# YOTSUBA_AP_EM_ver_3_0.net
KiCad netlist of a schematic drawn in EAGLE
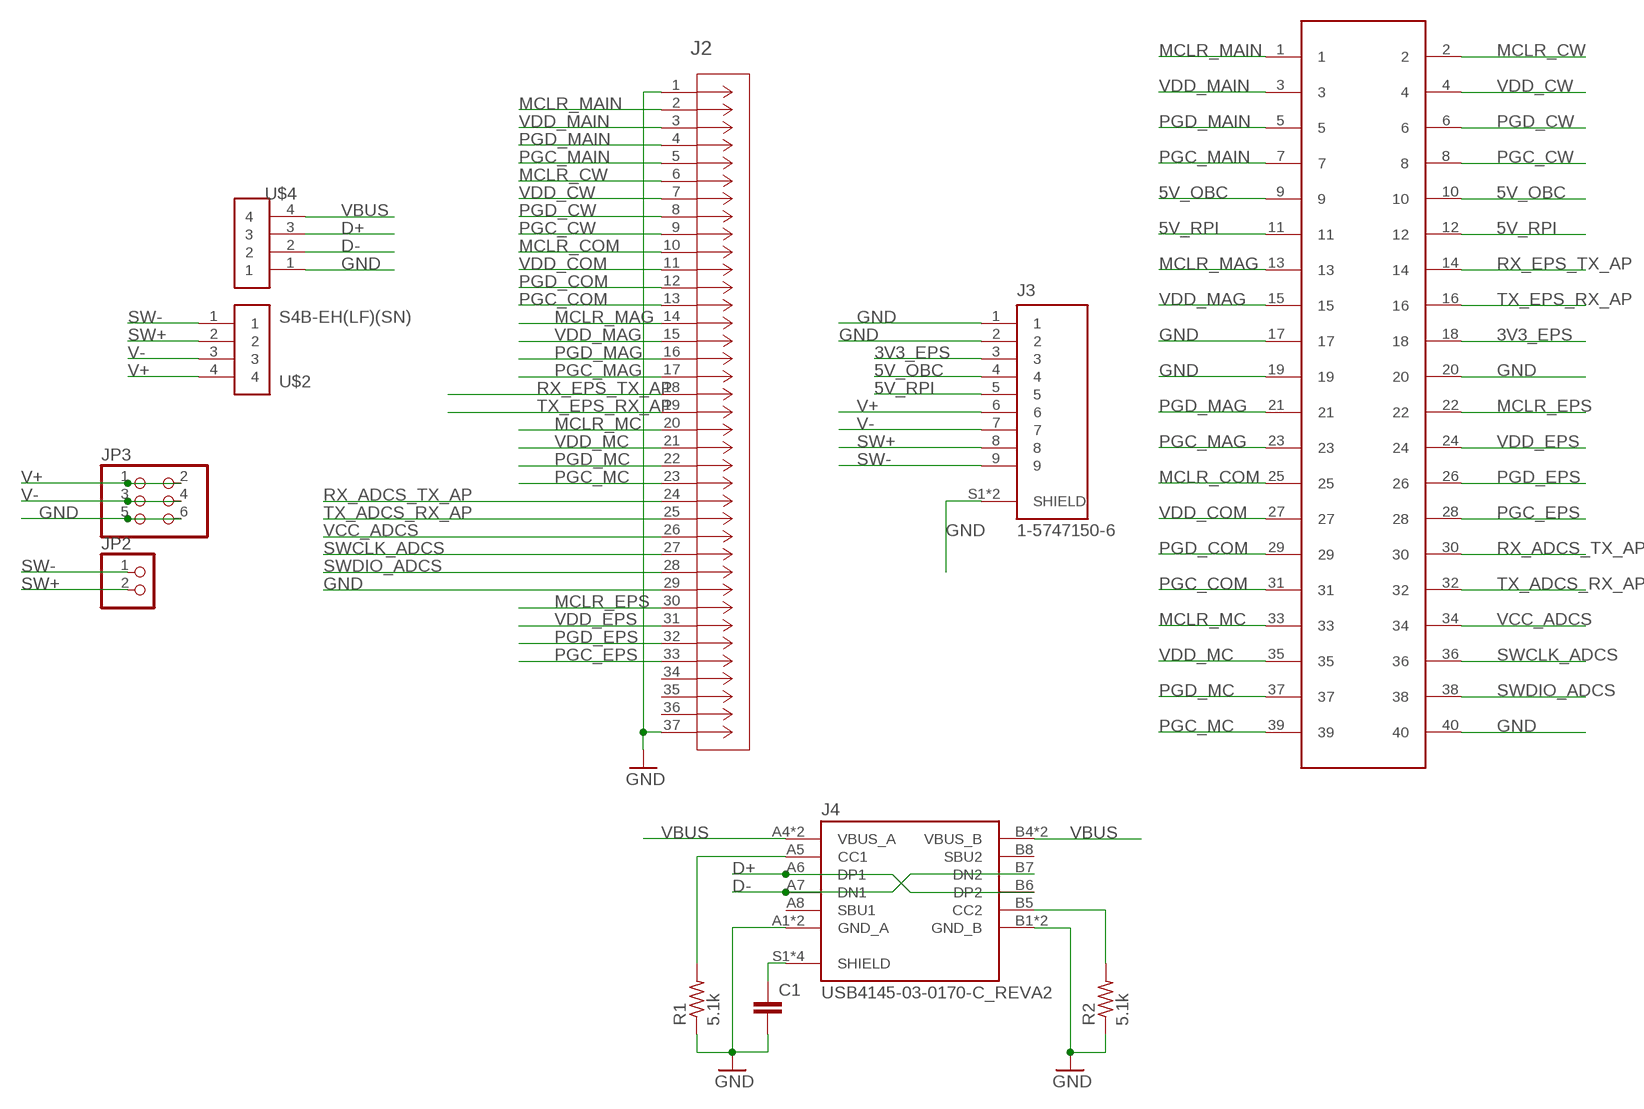
[diagram p0: schematic, sheet 1]

(export (version "E")
  (design (tool "Eeschema 10.0.6"))
  (components
    (comp (ref "C1")
      (value "C-EUC2012")
      (footprint "eagle-import:C2012")
      (libsource (lib "eagle-import") (part "C-EUC2012"))
    )
    (comp (ref "J2")
      (value "1-5747301-6")
      (footprint "eagle-import:CONN_1-5747301-6_TYC")
      (fields (field (name "COPYRIGHT") "Copyright (C) 2023 Ultra Librarian. All rights reserved."))
      (libsource (lib "eagle-import") (part "1-5747301-6"))
    )
    (comp (ref "J3")
      (value "1-5747150-6")
      (footprint "eagle-import:TE_1-5747150-6")
      (fields (field (name "MF") "TE Connectivity"))
      (libsource (lib "eagle-import") (part "1-5747150-6"))
    )
    (comp (ref "J4")
      (value "USB4145-03-0170-C_REVA2")
      (footprint "eagle-import:GCT_USB4145-03-0170-C_REVA2")
      (fields (field (name "MF") "Global Connector Technology") (field (name "MP") "USB4145-03-0170-C"))
      (libsource (lib "eagle-import") (part "USB4145-03-0170-C_REVA2"))
    )
    (comp (ref "JP2")
      (value "PINHD-1X2")
      (footprint "eagle-import:1X02")
      (libsource (lib "eagle-import") (part "PINHD-1X2"))
    )
    (comp (ref "JP3")
      (value "PINHD-2X3")
      (footprint "eagle-import:2X03")
      (libsource (lib "eagle-import") (part "PINHD-2X3"))
    )
    (comp (ref "R1")
      (value "5.1k")
      (footprint "eagle-import:R0805")
      (libsource (lib "eagle-import") (part "R-US_R0805"))
    )
    (comp (ref "R2")
      (value "5.1k")
      (footprint "eagle-import:R0805")
      (libsource (lib "eagle-import") (part "R-US_R0805"))
    )
    (comp (ref "U$1")
      (value "M50-3902042")
      (footprint "eagle-import:M50-3902042")
      (libsource (lib "eagle-import") (part "M50-3902042"))
    )
    (comp (ref "U$2")
      (value "S4B-EH(LF)(SN)")
      (footprint "eagle-import:JST_S4B-EH(LF)(SN)")
      (fields (field (name "MF") "JST Sales"))
      (libsource (lib "eagle-import") (part "S4B-EH(LF)(SN)"))
    )
    (comp (ref "U$4")
      (value "S4B-EH(LF)(SN)")
      (footprint "eagle-import:JST_S4B-EH(LF)(SN)")
      (fields (field (name "MF") "JST Sales"))
      (libsource (lib "eagle-import") (part "S4B-EH(LF)(SN)"))
    )
  )
  (nets
    (net (code "1") (name "/3V3_EPS") (class "Default")
      (node (ref "J3") (pin "3") (pinfunction "3_3") (pintype "passive"))
      (node (ref "U$1") (pin "18") (pinfunction "18_18") (pintype "bidirectional"))
    )
    (net (code "2") (name "/5V_OBC") (class "Default")
      (node (ref "J3") (pin "4") (pinfunction "4_4") (pintype "passive"))
      (node (ref "U$1") (pin "10") (pinfunction "10_10") (pintype "bidirectional"))
      (node (ref "U$1") (pin "9") (pinfunction "9_9") (pintype "bidirectional"))
    )
    (net (code "3") (name "/5V_RPI") (class "Default")
      (node (ref "J3") (pin "5") (pinfunction "5_5") (pintype "passive"))
      (node (ref "U$1") (pin "11") (pinfunction "11_11") (pintype "bidirectional"))
      (node (ref "U$1") (pin "12") (pinfunction "12_12") (pintype "bidirectional"))
    )
    (net (code "4") (name "/D+") (class "Default")
      (node (ref "J4") (pin "A6") (pinfunction "DP1_A6") (pintype "bidirectional"))
      (node (ref "J4") (pin "B6") (pinfunction "DP2_B6") (pintype "bidirectional"))
      (node (ref "U$4") (pin "3") (pinfunction "3_3") (pintype "passive"))
    )
    (net (code "5") (name "/D-") (class "Default")
      (node (ref "J4") (pin "A7") (pinfunction "DN1_A7") (pintype "bidirectional"))
      (node (ref "J4") (pin "B7") (pinfunction "DN2_B7") (pintype "bidirectional"))
      (node (ref "U$4") (pin "2") (pinfunction "2_2") (pintype "passive"))
    )
    (net (code "6") (name "/MCLR_COM") (class "Default")
      (node (ref "J2") (pin "10") (pinfunction "10_10") (pintype "passive"))
      (node (ref "U$1") (pin "25") (pinfunction "25_25") (pintype "bidirectional"))
    )
    (net (code "7") (name "/MCLR_CW") (class "Default")
      (node (ref "J2") (pin "6") (pinfunction "6_6") (pintype "passive"))
      (node (ref "U$1") (pin "2") (pinfunction "2_2") (pintype "bidirectional"))
    )
    (net (code "8") (name "/MCLR_EPS") (class "Default")
      (node (ref "J2") (pin "30") (pinfunction "30_30") (pintype "passive"))
      (node (ref "U$1") (pin "22") (pinfunction "22_22") (pintype "bidirectional"))
    )
    (net (code "9") (name "/MCLR_MAG") (class "Default")
      (node (ref "J2") (pin "14") (pinfunction "14_14") (pintype "passive"))
      (node (ref "U$1") (pin "13") (pinfunction "13_13") (pintype "bidirectional"))
    )
    (net (code "10") (name "/MCLR_MAIN") (class "Default")
      (node (ref "J2") (pin "2") (pinfunction "2_2") (pintype "passive"))
      (node (ref "U$1") (pin "1") (pinfunction "1_1") (pintype "bidirectional"))
    )
    (net (code "11") (name "/MCLR_MC") (class "Default")
      (node (ref "J2") (pin "20") (pinfunction "20_20") (pintype "passive"))
      (node (ref "U$1") (pin "33") (pinfunction "33_33") (pintype "bidirectional"))
    )
    (net (code "12") (name "/PGC_COM") (class "Default")
      (node (ref "J2") (pin "13") (pinfunction "13_13") (pintype "passive"))
      (node (ref "U$1") (pin "31") (pinfunction "31_31") (pintype "bidirectional"))
    )
    (net (code "13") (name "/PGC_CW") (class "Default")
      (node (ref "J2") (pin "9") (pinfunction "9_9") (pintype "passive"))
      (node (ref "U$1") (pin "8") (pinfunction "8_8") (pintype "bidirectional"))
    )
    (net (code "14") (name "/PGC_EPS") (class "Default")
      (node (ref "J2") (pin "33") (pinfunction "33_33") (pintype "passive"))
      (node (ref "U$1") (pin "28") (pinfunction "28_28") (pintype "bidirectional"))
    )
    (net (code "15") (name "/PGC_MAG") (class "Default")
      (node (ref "J2") (pin "17") (pinfunction "17_17") (pintype "passive"))
      (node (ref "U$1") (pin "23") (pinfunction "23_23") (pintype "bidirectional"))
    )
    (net (code "16") (name "/PGC_MAIN") (class "Default")
      (node (ref "J2") (pin "5") (pinfunction "5_5") (pintype "passive"))
      (node (ref "U$1") (pin "7") (pinfunction "7_7") (pintype "bidirectional"))
    )
    (net (code "17") (name "/PGC_MC") (class "Default")
      (node (ref "J2") (pin "23") (pinfunction "23_23") (pintype "passive"))
      (node (ref "U$1") (pin "39") (pinfunction "39_39") (pintype "bidirectional"))
    )
    (net (code "18") (name "/PGD_COM") (class "Default")
      (node (ref "J2") (pin "12") (pinfunction "12_12") (pintype "passive"))
      (node (ref "U$1") (pin "29") (pinfunction "29_29") (pintype "bidirectional"))
    )
    (net (code "19") (name "/PGD_CW") (class "Default")
      (node (ref "J2") (pin "8") (pinfunction "8_8") (pintype "passive"))
      (node (ref "U$1") (pin "6") (pinfunction "6_6") (pintype "bidirectional"))
    )
    (net (code "20") (name "/PGD_EPS") (class "Default")
      (node (ref "J2") (pin "32") (pinfunction "32_32") (pintype "passive"))
      (node (ref "U$1") (pin "26") (pinfunction "26_26") (pintype "bidirectional"))
    )
    (net (code "21") (name "/PGD_MAG") (class "Default")
      (node (ref "J2") (pin "16") (pinfunction "16_16") (pintype "passive"))
      (node (ref "U$1") (pin "21") (pinfunction "21_21") (pintype "bidirectional"))
    )
    (net (code "22") (name "/PGD_MAIN") (class "Default")
      (node (ref "J2") (pin "4") (pinfunction "4_4") (pintype "passive"))
      (node (ref "U$1") (pin "5") (pinfunction "5_5") (pintype "bidirectional"))
    )
    (net (code "23") (name "/PGD_MC") (class "Default")
      (node (ref "J2") (pin "22") (pinfunction "22_22") (pintype "passive"))
      (node (ref "U$1") (pin "37") (pinfunction "37_37") (pintype "bidirectional"))
    )
    (net (code "24") (name "/RX_ADCS_TX_AP") (class "Default")
      (node (ref "J2") (pin "24") (pinfunction "24_24") (pintype "passive"))
      (node (ref "U$1") (pin "30") (pinfunction "30_30") (pintype "bidirectional"))
    )
    (net (code "25") (name "/RX_EPS_TX_AP") (class "Default")
      (node (ref "J2") (pin "18") (pinfunction "18_18") (pintype "passive"))
      (node (ref "U$1") (pin "14") (pinfunction "14_14") (pintype "bidirectional"))
    )
    (net (code "26") (name "/SW+") (class "Default")
      (node (ref "J3") (pin "8") (pinfunction "8_8") (pintype "passive"))
      (node (ref "JP2") (pin "2") (pinfunction "2_2") (pintype "passive"))
      (node (ref "U$2") (pin "2") (pinfunction "2_2") (pintype "passive"))
    )
    (net (code "27") (name "/SW-") (class "Default")
      (node (ref "J3") (pin "9") (pinfunction "9_9") (pintype "passive"))
      (node (ref "JP2") (pin "1") (pinfunction "1_1") (pintype "passive"))
      (node (ref "U$2") (pin "1") (pinfunction "1_1") (pintype "passive"))
    )
    (net (code "28") (name "/SWCLK_ADCS") (class "Default")
      (node (ref "J2") (pin "27") (pinfunction "27_27") (pintype "passive"))
      (node (ref "U$1") (pin "36") (pinfunction "36_36") (pintype "bidirectional"))
    )
    (net (code "29") (name "/SWDIO_ADCS") (class "Default")
      (node (ref "J2") (pin "28") (pinfunction "28_28") (pintype "passive"))
      (node (ref "U$1") (pin "38") (pinfunction "38_38") (pintype "bidirectional"))
    )
    (net (code "30") (name "/TX_ADCS_RX_AP") (class "Default")
      (node (ref "J2") (pin "25") (pinfunction "25_25") (pintype "passive"))
      (node (ref "U$1") (pin "32") (pinfunction "32_32") (pintype "bidirectional"))
    )
    (net (code "31") (name "/TX_EPS_RX_AP") (class "Default")
      (node (ref "J2") (pin "19") (pinfunction "19_19") (pintype "passive"))
      (node (ref "U$1") (pin "16") (pinfunction "16_16") (pintype "bidirectional"))
    )
    (net (code "32") (name "/V+") (class "Default")
      (node (ref "J3") (pin "6") (pinfunction "6_6") (pintype "passive"))
      (node (ref "JP3") (pin "1") (pinfunction "1_1") (pintype "passive"))
      (node (ref "JP3") (pin "2") (pinfunction "2_2") (pintype "passive"))
      (node (ref "U$2") (pin "4") (pinfunction "4_4") (pintype "passive"))
    )
    (net (code "33") (name "/V-") (class "Default")
      (node (ref "J3") (pin "7") (pinfunction "7_7") (pintype "passive"))
      (node (ref "JP3") (pin "3") (pinfunction "3_3") (pintype "passive"))
      (node (ref "JP3") (pin "4") (pinfunction "4_4") (pintype "passive"))
      (node (ref "U$2") (pin "3") (pinfunction "3_3") (pintype "passive"))
    )
    (net (code "34") (name "/VBUS") (class "Default")
      (node (ref "J4") (pin "A4") (pinfunction "VBUS_A_A4") (pintype "power_in"))
      (node (ref "J4") (pin "A9") (pinfunction "VBUS_A_A9") (pintype "power_in"))
      (node (ref "J4") (pin "B4") (pinfunction "VBUS_B_B4") (pintype "power_in"))
      (node (ref "J4") (pin "B9") (pinfunction "VBUS_B_B9") (pintype "power_in"))
      (node (ref "U$4") (pin "4") (pinfunction "4_4") (pintype "passive"))
    )
    (net (code "35") (name "/VCC_ADCS") (class "Default")
      (node (ref "J2") (pin "26") (pinfunction "26_26") (pintype "passive"))
      (node (ref "U$1") (pin "34") (pinfunction "34_34") (pintype "bidirectional"))
    )
    (net (code "36") (name "/VDD_COM") (class "Default")
      (node (ref "J2") (pin "11") (pinfunction "11_11") (pintype "passive"))
      (node (ref "U$1") (pin "27") (pinfunction "27_27") (pintype "bidirectional"))
    )
    (net (code "37") (name "/VDD_CW") (class "Default")
      (node (ref "J2") (pin "7") (pinfunction "7_7") (pintype "passive"))
      (node (ref "U$1") (pin "4") (pinfunction "4_4") (pintype "bidirectional"))
    )
    (net (code "38") (name "/VDD_EPS") (class "Default")
      (node (ref "J2") (pin "31") (pinfunction "31_31") (pintype "passive"))
      (node (ref "U$1") (pin "24") (pinfunction "24_24") (pintype "bidirectional"))
    )
    (net (code "39") (name "/VDD_MAG") (class "Default")
      (node (ref "J2") (pin "15") (pinfunction "15_15") (pintype "passive"))
      (node (ref "U$1") (pin "15") (pinfunction "15_15") (pintype "bidirectional"))
    )
    (net (code "40") (name "/VDD_MAIN") (class "Default")
      (node (ref "J2") (pin "3") (pinfunction "3_3") (pintype "passive"))
      (node (ref "U$1") (pin "3") (pinfunction "3_3") (pintype "bidirectional"))
    )
    (net (code "41") (name "/VDD_MC") (class "Default")
      (node (ref "J2") (pin "21") (pinfunction "21_21") (pintype "passive"))
      (node (ref "U$1") (pin "35") (pinfunction "35_35") (pintype "bidirectional"))
    )
    (net (code "42") (name "GND") (class "Default")
      (node (ref "C1") (pin "2") (pinfunction "2_2") (pintype "passive"))
      (node (ref "J2") (pin "1") (pinfunction "1_1") (pintype "passive"))
      (node (ref "J2") (pin "29") (pinfunction "29_29") (pintype "passive"))
      (node (ref "J2") (pin "37") (pinfunction "37_37") (pintype "passive"))
      (node (ref "J3") (pin "1") (pinfunction "1_1") (pintype "passive"))
      (node (ref "J3") (pin "2") (pinfunction "2_2") (pintype "passive"))
      (node (ref "J3") (pin "S1") (pinfunction "SHIELD_S1") (pintype "passive"))
      (node (ref "J3") (pin "S2") (pinfunction "SHIELD_S2") (pintype "passive"))
      (node (ref "J4") (pin "A1") (pinfunction "GND_A_A1") (pintype "power_in"))
      (node (ref "J4") (pin "A12") (pinfunction "GND_A_A12") (pintype "power_in"))
      (node (ref "J4") (pin "B1") (pinfunction "GND_B_B1") (pintype "power_in"))
      (node (ref "J4") (pin "B12") (pinfunction "GND_B_B12") (pintype "power_in"))
      (node (ref "JP3") (pin "5") (pinfunction "5_5") (pintype "passive"))
      (node (ref "JP3") (pin "6") (pinfunction "6_6") (pintype "passive"))
      (node (ref "R1") (pin "1") (pinfunction "1_1") (pintype "passive"))
      (node (ref "R2") (pin "1") (pinfunction "1_1") (pintype "passive"))
      (node (ref "U$1") (pin "17") (pinfunction "17_17") (pintype "bidirectional"))
      (node (ref "U$1") (pin "19") (pinfunction "19_19") (pintype "bidirectional"))
      (node (ref "U$1") (pin "20") (pinfunction "20_20") (pintype "bidirectional"))
      (node (ref "U$1") (pin "40") (pinfunction "40_40") (pintype "bidirectional"))
      (node (ref "U$4") (pin "1") (pinfunction "1_1") (pintype "passive"))
    )
    (net (code "43") (name "Net-(C1-Pad1)") (class "Default")
      (node (ref "C1") (pin "1") (pinfunction "1_1") (pintype "passive"))
      (node (ref "J4") (pin "S1") (pinfunction "SHIELD_S1") (pintype "passive"))
      (node (ref "J4") (pin "S2") (pinfunction "SHIELD_S2") (pintype "passive"))
      (node (ref "J4") (pin "S3") (pinfunction "SHIELD_S3") (pintype "passive"))
      (node (ref "J4") (pin "S4") (pinfunction "SHIELD_S4") (pintype "passive"))
    )
    (net (code "44") (name "Net-(J4-CC1)") (class "Default")
      (node (ref "J4") (pin "A5") (pinfunction "CC1_A5") (pintype "bidirectional"))
      (node (ref "R1") (pin "2") (pinfunction "2_2") (pintype "passive"))
    )
    (net (code "45") (name "Net-(J4-CC2)") (class "Default")
      (node (ref "J4") (pin "B5") (pinfunction "CC2_B5") (pintype "bidirectional"))
      (node (ref "R2") (pin "2") (pinfunction "2_2") (pintype "passive"))
    )
    (net (code "46") (name "unconnected-(J2-Pad34)") (class "Default")
      (node (ref "J2") (pin "34") (pinfunction "34_34") (pintype "passive"))
    )
    (net (code "47") (name "unconnected-(J2-Pad35)") (class "Default")
      (node (ref "J2") (pin "35") (pinfunction "35_35") (pintype "passive"))
    )
    (net (code "48") (name "unconnected-(J2-Pad36)") (class "Default")
      (node (ref "J2") (pin "36") (pinfunction "36_36") (pintype "passive"))
    )
    (net (code "49") (name "unconnected-(J4-SBU1-PadA8)") (class "Default")
      (node (ref "J4") (pin "A8") (pinfunction "SBU1_A8") (pintype "bidirectional"))
    )
    (net (code "50") (name "unconnected-(J4-SBU2-PadB8)") (class "Default")
      (node (ref "J4") (pin "B8") (pinfunction "SBU2_B8") (pintype "bidirectional"))
    )
  )
)
